# ESP32-WROVER_Dev_Board.net
KiCad netlist of a schematic drawn in Altium Designer
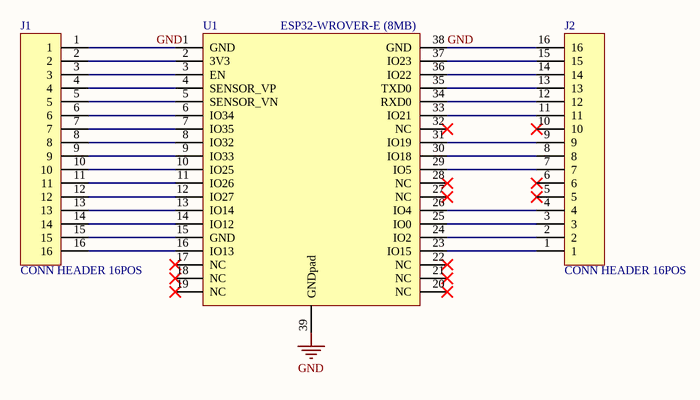
[diagram p0: ESP32-WROVER Dev Board.SchDoc]

(export (version "E")
  (design (tool "Eeschema 10.0.6"))
  (components
    (comp (ref "J1")
      (value "CONN HEADER 16POS")
      (footprint "CONN HEADER 16POS")
      (libsource (lib "G02_WSN") (part "CONN HEADER 16POS"))
    )
    (comp (ref "J2")
      (value "CONN HEADER 16POS")
      (footprint "CONN HEADER 16POS")
      (libsource (lib "") (part "CONN HEADER 16POS_1"))
    )
    (comp (ref "U1")
      (value "ESP32-WROVER-E (8MB)")
      (footprint "ESP32-WROVER-E (8MB)")
      (libsource (lib "G02_WSN") (part "ESP32-WROVER-E (8MB)"))
    )
  )
  (nets
    (net (code "1") (name "GND") (class "Default")
      (node (ref "J1") (pin "1") (pinfunction "1_1") (pintype "passive"))
      (node (ref "J2") (pin "16") (pinfunction "16_16") (pintype "passive"))
      (node (ref "U1") (pin "1") (pinfunction "GND_1") (pintype "passive"))
      (node (ref "U1") (pin "38") (pinfunction "GND_38") (pintype "passive"))
      (node (ref "U1") (pin "39") (pinfunction "GNDpad_39") (pintype "passive"))
    )
    (net (code "2") (name "Net-(J1-Pad15)") (class "Default")
      (node (ref "J1") (pin "15") (pinfunction "15_15") (pintype "passive"))
      (node (ref "U1") (pin "15") (pinfunction "GND_15") (pintype "passive"))
    )
    (net (code "3") (name "Net-(U1-3V3)") (class "Default")
      (node (ref "J1") (pin "2") (pinfunction "2_2") (pintype "passive"))
      (node (ref "U1") (pin "2") (pinfunction "3V3_2") (pintype "passive"))
    )
    (net (code "4") (name "Net-(U1-EN)") (class "Default")
      (node (ref "J1") (pin "3") (pinfunction "3_3") (pintype "passive"))
      (node (ref "U1") (pin "3") (pinfunction "EN_3") (pintype "passive"))
    )
    (net (code "5") (name "Net-(U1-IO0)") (class "Default")
      (node (ref "J2") (pin "3") (pinfunction "3_3") (pintype "passive"))
      (node (ref "U1") (pin "25") (pinfunction "IO0_25") (pintype "passive"))
    )
    (net (code "6") (name "Net-(U1-IO2)") (class "Default")
      (node (ref "J2") (pin "2") (pinfunction "2_2") (pintype "passive"))
      (node (ref "U1") (pin "24") (pinfunction "IO2_24") (pintype "passive"))
    )
    (net (code "7") (name "Net-(U1-IO4)") (class "Default")
      (node (ref "J2") (pin "4") (pinfunction "4_4") (pintype "passive"))
      (node (ref "U1") (pin "26") (pinfunction "IO4_26") (pintype "passive"))
    )
    (net (code "8") (name "Net-(U1-IO5)") (class "Default")
      (node (ref "J2") (pin "7") (pinfunction "7_7") (pintype "passive"))
      (node (ref "U1") (pin "29") (pinfunction "IO5_29") (pintype "passive"))
    )
    (net (code "9") (name "Net-(U1-IO12)") (class "Default")
      (node (ref "J1") (pin "14") (pinfunction "14_14") (pintype "passive"))
      (node (ref "U1") (pin "14") (pinfunction "IO12_14") (pintype "passive"))
    )
    (net (code "10") (name "Net-(U1-IO13)") (class "Default")
      (node (ref "J1") (pin "16") (pinfunction "16_16") (pintype "passive"))
      (node (ref "U1") (pin "16") (pinfunction "IO13_16") (pintype "passive"))
    )
    (net (code "11") (name "Net-(U1-IO14)") (class "Default")
      (node (ref "J1") (pin "13") (pinfunction "13_13") (pintype "passive"))
      (node (ref "U1") (pin "13") (pinfunction "IO14_13") (pintype "passive"))
    )
    (net (code "12") (name "Net-(U1-IO15)") (class "Default")
      (node (ref "J2") (pin "1") (pinfunction "1_1") (pintype "passive"))
      (node (ref "U1") (pin "23") (pinfunction "IO15_23") (pintype "passive"))
    )
    (net (code "13") (name "Net-(U1-IO18)") (class "Default")
      (node (ref "J2") (pin "8") (pinfunction "8_8") (pintype "passive"))
      (node (ref "U1") (pin "30") (pinfunction "IO18_30") (pintype "passive"))
    )
    (net (code "14") (name "Net-(U1-IO19)") (class "Default")
      (node (ref "J2") (pin "9") (pinfunction "9_9") (pintype "passive"))
      (node (ref "U1") (pin "31") (pinfunction "IO19_31") (pintype "passive"))
    )
    (net (code "15") (name "Net-(U1-IO21)") (class "Default")
      (node (ref "J2") (pin "11") (pinfunction "11_11") (pintype "passive"))
      (node (ref "U1") (pin "33") (pinfunction "IO21_33") (pintype "passive"))
    )
    (net (code "16") (name "Net-(U1-IO22)") (class "Default")
      (node (ref "J2") (pin "14") (pinfunction "14_14") (pintype "passive"))
      (node (ref "U1") (pin "36") (pinfunction "IO22_36") (pintype "passive"))
    )
    (net (code "17") (name "Net-(U1-IO23)") (class "Default")
      (node (ref "J2") (pin "15") (pinfunction "15_15") (pintype "passive"))
      (node (ref "U1") (pin "37") (pinfunction "IO23_37") (pintype "passive"))
    )
    (net (code "18") (name "Net-(U1-IO25)") (class "Default")
      (node (ref "J1") (pin "10") (pinfunction "10_10") (pintype "passive"))
      (node (ref "U1") (pin "10") (pinfunction "IO25_10") (pintype "passive"))
    )
    (net (code "19") (name "Net-(U1-IO26)") (class "Default")
      (node (ref "J1") (pin "11") (pinfunction "11_11") (pintype "passive"))
      (node (ref "U1") (pin "11") (pinfunction "IO26_11") (pintype "passive"))
    )
    (net (code "20") (name "Net-(U1-IO27)") (class "Default")
      (node (ref "J1") (pin "12") (pinfunction "12_12") (pintype "passive"))
      (node (ref "U1") (pin "12") (pinfunction "IO27_12") (pintype "passive"))
    )
    (net (code "21") (name "Net-(U1-IO32)") (class "Default")
      (node (ref "J1") (pin "8") (pinfunction "8_8") (pintype "passive"))
      (node (ref "U1") (pin "8") (pinfunction "IO32_8") (pintype "passive"))
    )
    (net (code "22") (name "Net-(U1-IO33)") (class "Default")
      (node (ref "J1") (pin "9") (pinfunction "9_9") (pintype "passive"))
      (node (ref "U1") (pin "9") (pinfunction "IO33_9") (pintype "passive"))
    )
    (net (code "23") (name "Net-(U1-IO34)") (class "Default")
      (node (ref "J1") (pin "6") (pinfunction "6_6") (pintype "passive"))
      (node (ref "U1") (pin "6") (pinfunction "IO34_6") (pintype "passive"))
    )
    (net (code "24") (name "Net-(U1-IO35)") (class "Default")
      (node (ref "J1") (pin "7") (pinfunction "7_7") (pintype "passive"))
      (node (ref "U1") (pin "7") (pinfunction "IO35_7") (pintype "passive"))
    )
    (net (code "25") (name "Net-(U1-RXD0)") (class "Default")
      (node (ref "J2") (pin "12") (pinfunction "12_12") (pintype "passive"))
      (node (ref "U1") (pin "34") (pinfunction "RXD0_34") (pintype "passive"))
    )
    (net (code "26") (name "Net-(U1-SENSOR_VN)") (class "Default")
      (node (ref "J1") (pin "5") (pinfunction "5_5") (pintype "passive"))
      (node (ref "U1") (pin "5") (pinfunction "SENSOR_VN_5") (pintype "passive"))
    )
    (net (code "27") (name "Net-(U1-SENSOR_VP)") (class "Default")
      (node (ref "J1") (pin "4") (pinfunction "4_4") (pintype "passive"))
      (node (ref "U1") (pin "4") (pinfunction "SENSOR_VP_4") (pintype "passive"))
    )
    (net (code "28") (name "Net-(U1-TXD0)") (class "Default")
      (node (ref "J2") (pin "13") (pinfunction "13_13") (pintype "passive"))
      (node (ref "U1") (pin "35") (pinfunction "TXD0_35") (pintype "passive"))
    )
    (net (code "29") (name "unconnected-(J2-Pad5)") (class "Default")
      (node (ref "J2") (pin "5") (pinfunction "5_5") (pintype "passive+no_connect"))
    )
    (net (code "30") (name "unconnected-(J2-Pad6)") (class "Default")
      (node (ref "J2") (pin "6") (pinfunction "6_6") (pintype "passive+no_connect"))
    )
    (net (code "31") (name "unconnected-(J2-Pad10)") (class "Default")
      (node (ref "J2") (pin "10") (pinfunction "10_10") (pintype "passive+no_connect"))
    )
    (net (code "32") (name "unconnected-(U1-NC-Pad17)") (class "Default")
      (node (ref "U1") (pin "17") (pinfunction "NC_17") (pintype "passive+no_connect"))
    )
    (net (code "33") (name "unconnected-(U1-NC-Pad18)") (class "Default")
      (node (ref "U1") (pin "18") (pinfunction "NC_18") (pintype "passive+no_connect"))
    )
    (net (code "34") (name "unconnected-(U1-NC-Pad19)") (class "Default")
      (node (ref "U1") (pin "19") (pinfunction "NC_19") (pintype "passive+no_connect"))
    )
    (net (code "35") (name "unconnected-(U1-NC-Pad20)") (class "Default")
      (node (ref "U1") (pin "20") (pinfunction "NC_20") (pintype "passive+no_connect"))
    )
    (net (code "36") (name "unconnected-(U1-NC-Pad21)") (class "Default")
      (node (ref "U1") (pin "21") (pinfunction "NC_21") (pintype "passive+no_connect"))
    )
    (net (code "37") (name "unconnected-(U1-NC-Pad22)") (class "Default")
      (node (ref "U1") (pin "22") (pinfunction "NC_22") (pintype "passive+no_connect"))
    )
    (net (code "38") (name "unconnected-(U1-NC-Pad27)") (class "Default")
      (node (ref "U1") (pin "27") (pinfunction "NC_27") (pintype "passive+no_connect"))
    )
    (net (code "39") (name "unconnected-(U1-NC-Pad28)") (class "Default")
      (node (ref "U1") (pin "28") (pinfunction "NC_28") (pintype "passive+no_connect"))
    )
    (net (code "40") (name "unconnected-(U1-NC-Pad32)") (class "Default")
      (node (ref "U1") (pin "32") (pinfunction "NC_32") (pintype "passive+no_connect"))
    )
  )
)
